# FPGA_MGT.net
KiCad netlist of a schematic drawn in Altium Designer
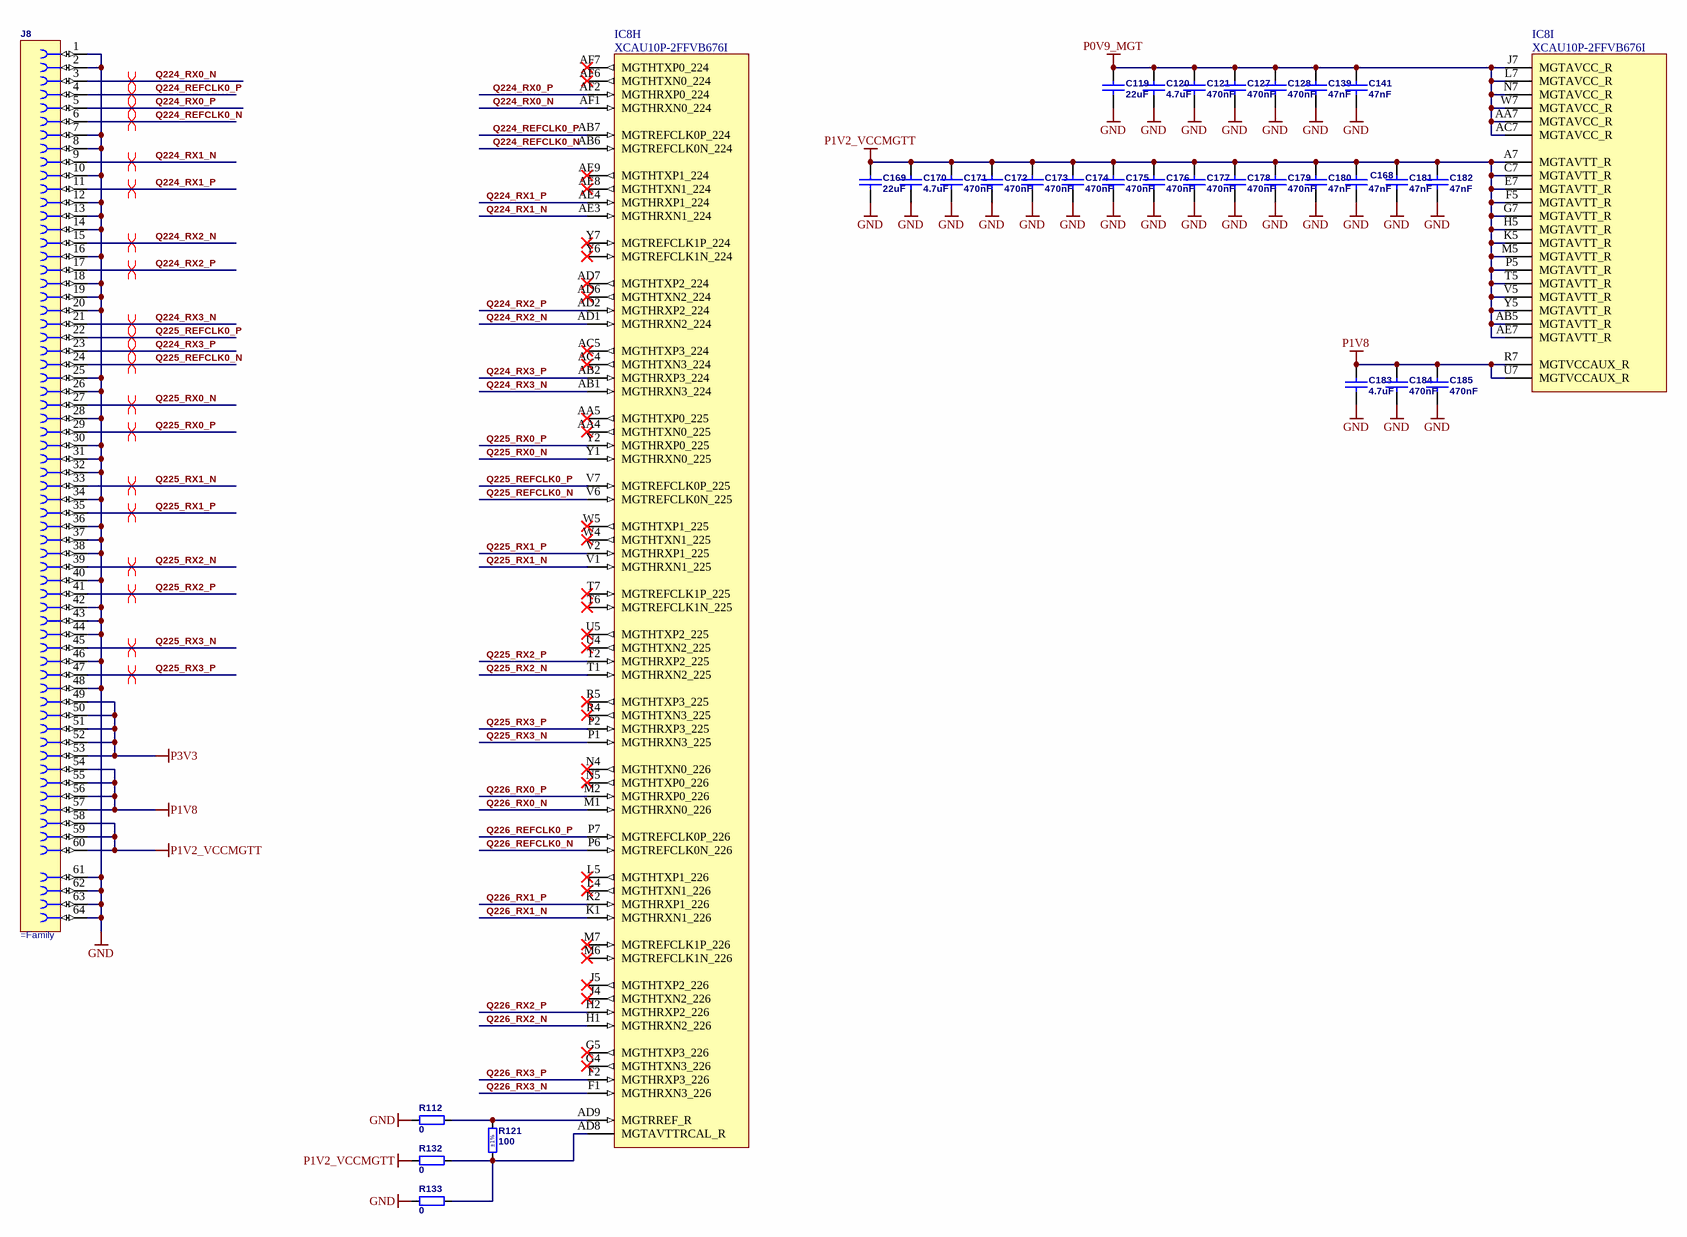
[diagram p0: FPGA_MGT.SchDoc]

(export (version "E")
  (design (tool "Eeschema 10.0.6"))
  (components
    (comp (ref "C119")
      (value "22uF")
      (footprint "CAPC1608X90N")
      (description "Non-polarised capacitor")
      (fields
        (field (name "PART NUMBER") "CC0603_22UF_6.3V_20%_X5R")
        (field (name "VOLTAGE") "6.3V")
        (field (name "AUTHOR") "CERN DEM JLC")
      )
      (libsource (lib "Capacitors") (part "Capacitor - non polarized"))
    )
    (comp (ref "C120")
      (value "4.7uF")
      (footprint "CAPC2012X135N")
      (description "Non-polarised capacitor")
      (fields
        (field (name "PART NUMBER") "CC0805_4.7UF_16V_10%_X7R")
        (field (name "VOLTAGE") "16V")
        (field (name "AUTHOR") "CERN DEM JLC")
      )
      (libsource (lib "Capacitors") (part "Capacitor - non polarized"))
    )
    (comp (ref "C121")
      (value "470nF")
      (footprint "CAPC1005X55N")
      (description "Non-polarised capacitor")
      (fields
        (field (name "PART NUMBER") "CC0402_470NF_16V_10%_X5R")
        (field (name "VOLTAGE") "16V")
        (field (name "AUTHOR") "CERN DEM JLC")
      )
      (libsource (lib "Capacitors") (part "Capacitor - non polarized"))
    )
    (comp (ref "C127")
      (value "470nF")
      (footprint "CAPC1005X55N")
      (description "Non-polarised capacitor")
      (fields
        (field (name "PART NUMBER") "CC0402_470NF_16V_10%_X5R")
        (field (name "VOLTAGE") "16V")
        (field (name "AUTHOR") "CERN DEM JLC")
      )
      (libsource (lib "Capacitors") (part "Capacitor - non polarized"))
    )
    (comp (ref "C128")
      (value "470nF")
      (footprint "CAPC1005X55N")
      (description "Non-polarised capacitor")
      (fields
        (field (name "PART NUMBER") "CC0402_470NF_16V_10%_X5R")
        (field (name "VOLTAGE") "16V")
        (field (name "AUTHOR") "CERN DEM JLC")
      )
      (libsource (lib "Capacitors") (part "Capacitor - non polarized"))
    )
    (comp (ref "C139")
      (value "47nF")
      (footprint "CAPC1005X55N")
      (description "Non-polarised capacitor")
      (fields
        (field (name "PART NUMBER") "CC0402_47NF_16V_10%_X7R")
        (field (name "VOLTAGE") "16V")
        (field (name "AUTHOR") "CERN DEM JLC")
      )
      (libsource (lib "Capacitors") (part "Capacitor - non polarized"))
    )
    (comp (ref "C141")
      (value "47nF")
      (footprint "CAPC1005X55N")
      (description "Non-polarised capacitor")
      (fields
        (field (name "PART NUMBER") "CC0402_47NF_16V_10%_X7R")
        (field (name "VOLTAGE") "16V")
        (field (name "AUTHOR") "CERN DEM JLC")
      )
      (libsource (lib "Capacitors") (part "Capacitor - non polarized"))
    )
    (comp (ref "C168")
      (value "47nF")
      (footprint "CAPC1005X55N")
      (description "Non-polarised capacitor")
      (fields
        (field (name "PART NUMBER") "CC0402_47NF_16V_10%_X7R")
        (field (name "VOLTAGE") "16V")
        (field (name "AUTHOR") "CERN DEM JLC")
      )
      (libsource (lib "Capacitors") (part "Capacitor - non polarized"))
    )
    (comp (ref "C169")
      (value "22uF")
      (footprint "CAPC1608X90N")
      (description "Non-polarised capacitor")
      (fields
        (field (name "PART NUMBER") "CC0603_22UF_6.3V_20%_X5R")
        (field (name "VOLTAGE") "6.3V")
        (field (name "AUTHOR") "CERN DEM JLC")
      )
      (libsource (lib "Capacitors") (part "Capacitor - non polarized"))
    )
    (comp (ref "C170")
      (value "4.7uF")
      (footprint "CAPC2012X135N")
      (description "Non-polarised capacitor")
      (fields
        (field (name "PART NUMBER") "CC0805_4.7UF_16V_10%_X7R")
        (field (name "VOLTAGE") "16V")
        (field (name "AUTHOR") "CERN DEM JLC")
      )
      (libsource (lib "Capacitors") (part "Capacitor - non polarized"))
    )
    (comp (ref "C171")
      (value "470nF")
      (footprint "CAPC1005X55N")
      (description "Non-polarised capacitor")
      (fields
        (field (name "PART NUMBER") "CC0402_470NF_16V_10%_X5R")
        (field (name "VOLTAGE") "16V")
        (field (name "AUTHOR") "CERN DEM JLC")
      )
      (libsource (lib "Capacitors") (part "Capacitor - non polarized"))
    )
    (comp (ref "C172")
      (value "470nF")
      (footprint "CAPC1005X55N")
      (description "Non-polarised capacitor")
      (fields
        (field (name "PART NUMBER") "CC0402_470NF_16V_10%_X5R")
        (field (name "VOLTAGE") "16V")
        (field (name "AUTHOR") "CERN DEM JLC")
      )
      (libsource (lib "Capacitors") (part "Capacitor - non polarized"))
    )
    (comp (ref "C173")
      (value "470nF")
      (footprint "CAPC1005X55N")
      (description "Non-polarised capacitor")
      (fields
        (field (name "PART NUMBER") "CC0402_470NF_16V_10%_X5R")
        (field (name "VOLTAGE") "16V")
        (field (name "AUTHOR") "CERN DEM JLC")
      )
      (libsource (lib "Capacitors") (part "Capacitor - non polarized"))
    )
    (comp (ref "C174")
      (value "470nF")
      (footprint "CAPC1005X55N")
      (description "Non-polarised capacitor")
      (fields
        (field (name "PART NUMBER") "CC0402_470NF_16V_10%_X5R")
        (field (name "VOLTAGE") "16V")
        (field (name "AUTHOR") "CERN DEM JLC")
      )
      (libsource (lib "Capacitors") (part "Capacitor - non polarized"))
    )
    (comp (ref "C175")
      (value "470nF")
      (footprint "CAPC1005X55N")
      (description "Non-polarised capacitor")
      (fields
        (field (name "PART NUMBER") "CC0402_470NF_16V_10%_X5R")
        (field (name "VOLTAGE") "16V")
        (field (name "AUTHOR") "CERN DEM JLC")
      )
      (libsource (lib "Capacitors") (part "Capacitor - non polarized"))
    )
    (comp (ref "C176")
      (value "470nF")
      (footprint "CAPC1005X55N")
      (description "Non-polarised capacitor")
      (fields
        (field (name "PART NUMBER") "CC0402_470NF_16V_10%_X5R")
        (field (name "VOLTAGE") "16V")
        (field (name "AUTHOR") "CERN DEM JLC")
      )
      (libsource (lib "Capacitors") (part "Capacitor - non polarized"))
    )
    (comp (ref "C177")
      (value "470nF")
      (footprint "CAPC1005X55N")
      (description "Non-polarised capacitor")
      (fields
        (field (name "PART NUMBER") "CC0402_470NF_16V_10%_X5R")
        (field (name "VOLTAGE") "16V")
        (field (name "AUTHOR") "CERN DEM JLC")
      )
      (libsource (lib "Capacitors") (part "Capacitor - non polarized"))
    )
    (comp (ref "C178")
      (value "470nF")
      (footprint "CAPC1005X55N")
      (description "Non-polarised capacitor")
      (fields
        (field (name "PART NUMBER") "CC0402_470NF_16V_10%_X5R")
        (field (name "VOLTAGE") "16V")
        (field (name "AUTHOR") "CERN DEM JLC")
      )
      (libsource (lib "Capacitors") (part "Capacitor - non polarized"))
    )
    (comp (ref "C179")
      (value "470nF")
      (footprint "CAPC1005X55N")
      (description "Non-polarised capacitor")
      (fields
        (field (name "PART NUMBER") "CC0402_470NF_16V_10%_X5R")
        (field (name "VOLTAGE") "16V")
        (field (name "AUTHOR") "CERN DEM JLC")
      )
      (libsource (lib "Capacitors") (part "Capacitor - non polarized"))
    )
    (comp (ref "C180")
      (value "47nF")
      (footprint "CAPC1005X55N")
      (description "Non-polarised capacitor")
      (fields
        (field (name "PART NUMBER") "CC0402_47NF_16V_10%_X7R")
        (field (name "VOLTAGE") "16V")
        (field (name "AUTHOR") "CERN DEM JLC")
      )
      (libsource (lib "Capacitors") (part "Capacitor - non polarized"))
    )
    (comp (ref "C181")
      (value "47nF")
      (footprint "CAPC1005X55N")
      (description "Non-polarised capacitor")
      (fields
        (field (name "PART NUMBER") "CC0402_47NF_16V_10%_X7R")
        (field (name "VOLTAGE") "16V")
        (field (name "AUTHOR") "CERN DEM JLC")
      )
      (libsource (lib "Capacitors") (part "Capacitor - non polarized"))
    )
    (comp (ref "C182")
      (value "47nF")
      (footprint "CAPC1005X55N")
      (description "Non-polarised capacitor")
      (fields
        (field (name "PART NUMBER") "CC0402_47NF_16V_10%_X7R")
        (field (name "VOLTAGE") "16V")
        (field (name "AUTHOR") "CERN DEM JLC")
      )
      (libsource (lib "Capacitors") (part "Capacitor - non polarized"))
    )
    (comp (ref "C183")
      (value "4.7uF")
      (footprint "CAPC2012X135N")
      (description "Non-polarised capacitor")
      (fields
        (field (name "PART NUMBER") "CC0805_4.7UF_16V_10%_X7R")
        (field (name "VOLTAGE") "16V")
        (field (name "AUTHOR") "CERN DEM JLC")
      )
      (libsource (lib "Capacitors") (part "Capacitor - non polarized"))
    )
    (comp (ref "C184")
      (value "470nF")
      (footprint "CAPC1005X55N")
      (description "Non-polarised capacitor")
      (fields
        (field (name "PART NUMBER") "CC0402_470NF_16V_10%_X5R")
        (field (name "VOLTAGE") "16V")
        (field (name "AUTHOR") "CERN DEM JLC")
      )
      (libsource (lib "Capacitors") (part "Capacitor - non polarized"))
    )
    (comp (ref "C185")
      (value "470nF")
      (footprint "CAPC1005X55N")
      (description "Non-polarised capacitor")
      (fields
        (field (name "PART NUMBER") "CC0402_470NF_16V_10%_X5R")
        (field (name "VOLTAGE") "16V")
        (field (name "AUTHOR") "CERN DEM JLC")
      )
      (libsource (lib "Capacitors") (part "Capacitor - non polarized"))
    )
    (comp (ref "IC8")
      (value "XCAU10P-2FFVB676I")
      (footprint "BGA676C100P26X26_2700X2700X350")
      (description "Artix UltraScale + Field Programmable Gate Array (FPGA), 676-Pin BGA, Industrial Grade")
      (fields (field (name "MANUFACTURER") "AMD") (field (name "AUTHOR") "CERN DEM HF"))
      (libsource (lib "ICs And Semiconductors") (part "XCAU10P-2FFVB676I"))
    )
    (comp (ref "J8")
      (value "~")
      (footprint "SAMTEC_QSH-030-01-L-D-A")
      (description "Connector 60 Female + 4 GND")
      (fields
        (field (name "PART NUMBER") "SAMTEC_QSH-030-01-L-D-A")
        (field (name "MANUFACTURER") "SAMTEC")
        (field (name "AUTHOR") "CERN DEM JLC")
      )
      (libsource (lib "Connectors") (part "Connector 60 Female + 4 GND"))
    )
    (comp (ref "R112")
      (value "0")
      (footprint "RESC1005X40N")
      (description "Resistor")
      (fields
        (field (name "PART NUMBER") "R0402_0R_JUMPER")
        (field (name "MANUFACTURER") "GENERIC")
        (field (name "AUTHOR") "CERN DEM JLC")
      )
      (libsource (lib "Resistors") (part "Resistor"))
    )
    (comp (ref "R121")
      (value "100")
      (footprint "RESC1005X40N")
      (description "Resistor - 1%")
      (fields
        (field (name "TOLERANCE") "±1%")
        (field (name "PART NUMBER") "R0402_100R_1%_0.0625W_100PPM")
        (field (name "POWER") "0.0625W")
        (field (name "AUTHOR") "CERN DEM JLC")
      )
      (libsource (lib "Resistors") (part "Resistor - 1%"))
    )
    (comp (ref "R132")
      (value "0")
      (footprint "RESC1005X40N")
      (description "Resistor")
      (fields
        (field (name "PART NUMBER") "R0402_0R_JUMPER")
        (field (name "MANUFACTURER") "GENERIC")
        (field (name "AUTHOR") "CERN DEM JLC")
      )
      (libsource (lib "Resistors") (part "Resistor"))
    )
    (comp (ref "R133")
      (value "0")
      (footprint "RESC1005X40N")
      (description "Resistor")
      (fields
        (field (name "PART NUMBER") "R0402_0R_JUMPER")
        (field (name "MANUFACTURER") "GENERIC")
        (field (name "AUTHOR") "CERN DEM JLC")
      )
      (libsource (lib "Resistors") (part "Resistor"))
    )
  )
  (nets
    (net (code "1") (name "/Q224_REFCLK0_N") (class "Default")
      (node (ref "IC8") (pin "AB6") (pinfunction "MGTREFCLK0N_224_AB6") (pintype "input"))
      (node (ref "J8") (pin "6") (pinfunction "6_6") (pintype "bidirectional"))
    )
    (net (code "2") (name "/Q224_REFCLK0_P") (class "Default")
      (node (ref "IC8") (pin "AB7") (pinfunction "MGTREFCLK0P_224_AB7") (pintype "input"))
      (node (ref "J8") (pin "4") (pinfunction "4_4") (pintype "bidirectional"))
    )
    (net (code "3") (name "/Q224_RX0_N") (class "Default")
      (node (ref "IC8") (pin "AF1") (pinfunction "MGTHRXN0_224_AF1") (pintype "input"))
      (node (ref "J8") (pin "3") (pinfunction "3_3") (pintype "bidirectional"))
    )
    (net (code "4") (name "/Q224_RX0_P") (class "Default")
      (node (ref "IC8") (pin "AF2") (pinfunction "MGTHRXP0_224_AF2") (pintype "input"))
      (node (ref "J8") (pin "5") (pinfunction "5_5") (pintype "bidirectional"))
    )
    (net (code "5") (name "/Q224_RX1_N") (class "Default")
      (node (ref "IC8") (pin "AE3") (pinfunction "MGTHRXN1_224_AE3") (pintype "input"))
      (node (ref "J8") (pin "9") (pinfunction "9_9") (pintype "bidirectional"))
    )
    (net (code "6") (name "/Q224_RX1_P") (class "Default")
      (node (ref "IC8") (pin "AE4") (pinfunction "MGTHRXP1_224_AE4") (pintype "input"))
      (node (ref "J8") (pin "11") (pinfunction "11_11") (pintype "bidirectional"))
    )
    (net (code "7") (name "/Q224_RX2_N") (class "Default")
      (node (ref "IC8") (pin "AD1") (pinfunction "MGTHRXN2_224_AD1") (pintype "input"))
      (node (ref "J8") (pin "15") (pinfunction "15_15") (pintype "bidirectional"))
    )
    (net (code "8") (name "/Q224_RX2_P") (class "Default")
      (node (ref "IC8") (pin "AD2") (pinfunction "MGTHRXP2_224_AD2") (pintype "input"))
      (node (ref "J8") (pin "17") (pinfunction "17_17") (pintype "bidirectional"))
    )
    (net (code "9") (name "/Q224_RX3_N") (class "Default")
      (node (ref "IC8") (pin "AB1") (pinfunction "MGTHRXN3_224_AB1") (pintype "input"))
      (node (ref "J8") (pin "21") (pinfunction "21_21") (pintype "bidirectional"))
    )
    (net (code "10") (name "/Q224_RX3_P") (class "Default")
      (node (ref "IC8") (pin "AB2") (pinfunction "MGTHRXP3_224_AB2") (pintype "input"))
      (node (ref "J8") (pin "23") (pinfunction "23_23") (pintype "bidirectional"))
    )
    (net (code "11") (name "/Q225_REFCLK0_N") (class "Default")
      (node (ref "IC8") (pin "V6") (pinfunction "MGTREFCLK0N_225_V6") (pintype "input"))
      (node (ref "J8") (pin "24") (pinfunction "24_24") (pintype "bidirectional"))
    )
    (net (code "12") (name "/Q225_REFCLK0_P") (class "Default")
      (node (ref "IC8") (pin "V7") (pinfunction "MGTREFCLK0P_225_V7") (pintype "input"))
      (node (ref "J8") (pin "22") (pinfunction "22_22") (pintype "bidirectional"))
    )
    (net (code "13") (name "/Q225_RX0_N") (class "Default")
      (node (ref "IC8") (pin "Y1") (pinfunction "MGTHRXN0_225_Y1") (pintype "input"))
      (node (ref "J8") (pin "27") (pinfunction "27_27") (pintype "bidirectional"))
    )
    (net (code "14") (name "/Q225_RX0_P") (class "Default")
      (node (ref "IC8") (pin "Y2") (pinfunction "MGTHRXP0_225_Y2") (pintype "input"))
      (node (ref "J8") (pin "29") (pinfunction "29_29") (pintype "bidirectional"))
    )
    (net (code "15") (name "/Q225_RX1_N") (class "Default")
      (node (ref "IC8") (pin "V1") (pinfunction "MGTHRXN1_225_V1") (pintype "input"))
      (node (ref "J8") (pin "33") (pinfunction "33_33") (pintype "bidirectional"))
    )
    (net (code "16") (name "/Q225_RX1_P") (class "Default")
      (node (ref "IC8") (pin "V2") (pinfunction "MGTHRXP1_225_V2") (pintype "input"))
      (node (ref "J8") (pin "35") (pinfunction "35_35") (pintype "bidirectional"))
    )
    (net (code "17") (name "/Q225_RX2_N") (class "Default")
      (node (ref "IC8") (pin "T1") (pinfunction "MGTHRXN2_225_T1") (pintype "input"))
      (node (ref "J8") (pin "39") (pinfunction "39_39") (pintype "bidirectional"))
    )
    (net (code "18") (name "/Q225_RX2_P") (class "Default")
      (node (ref "IC8") (pin "T2") (pinfunction "MGTHRXP2_225_T2") (pintype "input"))
      (node (ref "J8") (pin "41") (pinfunction "41_41") (pintype "bidirectional"))
    )
    (net (code "19") (name "/Q225_RX3_N") (class "Default")
      (node (ref "IC8") (pin "P1") (pinfunction "MGTHRXN3_225_P1") (pintype "input"))
      (node (ref "J8") (pin "45") (pinfunction "45_45") (pintype "bidirectional"))
    )
    (net (code "20") (name "/Q225_RX3_P") (class "Default")
      (node (ref "IC8") (pin "P2") (pinfunction "MGTHRXP3_225_P2") (pintype "input"))
      (node (ref "J8") (pin "47") (pinfunction "47_47") (pintype "bidirectional"))
    )
    (net (code "21") (name "/Q226_REFCLK0_N") (class "Default")
      (node (ref "IC8") (pin "P6") (pinfunction "MGTREFCLK0N_226_P6") (pintype "input"))
    )
    (net (code "22") (name "/Q226_REFCLK0_P") (class "Default")
      (node (ref "IC8") (pin "P7") (pinfunction "MGTREFCLK0P_226_P7") (pintype "input"))
    )
    (net (code "23") (name "/Q226_RX0_N") (class "Default")
      (node (ref "IC8") (pin "M1") (pinfunction "MGTHRXN0_226_M1") (pintype "input"))
    )
    (net (code "24") (name "/Q226_RX0_P") (class "Default")
      (node (ref "IC8") (pin "M2") (pinfunction "MGTHRXP0_226_M2") (pintype "input"))
    )
    (net (code "25") (name "/Q226_RX1_N") (class "Default")
      (node (ref "IC8") (pin "K1") (pinfunction "MGTHRXN1_226_K1") (pintype "input"))
    )
    (net (code "26") (name "/Q226_RX1_P") (class "Default")
      (node (ref "IC8") (pin "K2") (pinfunction "MGTHRXP1_226_K2") (pintype "input"))
    )
    (net (code "27") (name "/Q226_RX2_N") (class "Default")
      (node (ref "IC8") (pin "H1") (pinfunction "MGTHRXN2_226_H1") (pintype "input"))
    )
    (net (code "28") (name "/Q226_RX2_P") (class "Default")
      (node (ref "IC8") (pin "H2") (pinfunction "MGTHRXP2_226_H2") (pintype "input"))
    )
    (net (code "29") (name "/Q226_RX3_N") (class "Default")
      (node (ref "IC8") (pin "F1") (pinfunction "MGTHRXN3_226_F1") (pintype "input"))
    )
    (net (code "30") (name "/Q226_RX3_P") (class "Default")
      (node (ref "IC8") (pin "F2") (pinfunction "MGTHRXP3_226_F2") (pintype "input"))
    )
    (net (code "31") (name "GND") (class "Default")
      (node (ref "C119") (pin "1") (pinfunction "1_1") (pintype "passive"))
      (node (ref "C120") (pin "1") (pinfunction "1_1") (pintype "passive"))
      (node (ref "C121") (pin "1") (pinfunction "1_1") (pintype "passive"))
      (node (ref "C127") (pin "1") (pinfunction "1_1") (pintype "passive"))
      (node (ref "C128") (pin "1") (pinfunction "1_1") (pintype "passive"))
      (node (ref "C139") (pin "1") (pinfunction "1_1") (pintype "passive"))
      (node (ref "C141") (pin "1") (pinfunction "1_1") (pintype "passive"))
      (node (ref "C168") (pin "1") (pinfunction "1_1") (pintype "passive"))
      (node (ref "C169") (pin "1") (pinfunction "1_1") (pintype "passive"))
      (node (ref "C170") (pin "1") (pinfunction "1_1") (pintype "passive"))
      (node (ref "C171") (pin "1") (pinfunction "1_1") (pintype "passive"))
      (node (ref "C172") (pin "1") (pinfunction "1_1") (pintype "passive"))
      (node (ref "C173") (pin "1") (pinfunction "1_1") (pintype "passive"))
      (node (ref "C174") (pin "1") (pinfunction "1_1") (pintype "passive"))
      (node (ref "C175") (pin "1") (pinfunction "1_1") (pintype "passive"))
      (node (ref "C176") (pin "1") (pinfunction "1_1") (pintype "passive"))
      (node (ref "C177") (pin "1") (pinfunction "1_1") (pintype "passive"))
      (node (ref "C178") (pin "1") (pinfunction "1_1") (pintype "passive"))
      (node (ref "C179") (pin "1") (pinfunction "1_1") (pintype "passive"))
      (node (ref "C180") (pin "1") (pinfunction "1_1") (pintype "passive"))
      (node (ref "C181") (pin "1") (pinfunction "1_1") (pintype "passive"))
      (node (ref "C182") (pin "1") (pinfunction "1_1") (pintype "passive"))
      (node (ref "C183") (pin "1") (pinfunction "1_1") (pintype "passive"))
      (node (ref "C184") (pin "1") (pinfunction "1_1") (pintype "passive"))
      (node (ref "C185") (pin "1") (pinfunction "1_1") (pintype "passive"))
      (node (ref "J8") (pin "1") (pinfunction "1_1") (pintype "bidirectional"))
      (node (ref "J8") (pin "10") (pinfunction "10_10") (pintype "bidirectional"))
      (node (ref "J8") (pin "12") (pinfunction "12_12") (pintype "bidirectional"))
      (node (ref "J8") (pin "13") (pinfunction "13_13") (pintype "bidirectional"))
      (node (ref "J8") (pin "14") (pinfunction "14_14") (pintype "bidirectional"))
      (node (ref "J8") (pin "16") (pinfunction "16_16") (pintype "bidirectional"))
      (node (ref "J8") (pin "18") (pinfunction "18_18") (pintype "bidirectional"))
      (node (ref "J8") (pin "19") (pinfunction "19_19") (pintype "bidirectional"))
      (node (ref "J8") (pin "2") (pinfunction "2_2") (pintype "bidirectional"))
      (node (ref "J8") (pin "20") (pinfunction "20_20") (pintype "bidirectional"))
      (node (ref "J8") (pin "25") (pinfunction "25_25") (pintype "bidirectional"))
      (node (ref "J8") (pin "26") (pinfunction "26_26") (pintype "bidirectional"))
      (node (ref "J8") (pin "28") (pinfunction "28_28") (pintype "bidirectional"))
      (node (ref "J8") (pin "30") (pinfunction "30_30") (pintype "bidirectional"))
      (node (ref "J8") (pin "31") (pinfunction "31_31") (pintype "bidirectional"))
      (node (ref "J8") (pin "32") (pinfunction "32_32") (pintype "bidirectional"))
      (node (ref "J8") (pin "34") (pinfunction "34_34") (pintype "bidirectional"))
      (node (ref "J8") (pin "36") (pinfunction "36_36") (pintype "bidirectional"))
      (node (ref "J8") (pin "37") (pinfunction "37_37") (pintype "bidirectional"))
      (node (ref "J8") (pin "38") (pinfunction "38_38") (pintype "bidirectional"))
      (node (ref "J8") (pin "40") (pinfunction "40_40") (pintype "bidirectional"))
      (node (ref "J8") (pin "42") (pinfunction "42_42") (pintype "bidirectional"))
      (node (ref "J8") (pin "43") (pinfunction "43_43") (pintype "bidirectional"))
      (node (ref "J8") (pin "44") (pinfunction "44_44") (pintype "bidirectional"))
      (node (ref "J8") (pin "46") (pinfunction "46_46") (pintype "bidirectional"))
      (node (ref "J8") (pin "48") (pinfunction "48_48") (pintype "bidirectional"))
      (node (ref "J8") (pin "61") (pinfunction "61_61") (pintype "bidirectional"))
      (node (ref "J8") (pin "62") (pinfunction "62_62") (pintype "bidirectional"))
      (node (ref "J8") (pin "63") (pinfunction "63_63") (pintype "bidirectional"))
      (node (ref "J8") (pin "64") (pinfunction "64_64") (pintype "bidirectional"))
      (node (ref "J8") (pin "7") (pinfunction "7_7") (pintype "bidirectional"))
      (node (ref "J8") (pin "8") (pinfunction "8_8") (pintype "bidirectional"))
      (node (ref "R112") (pin "1") (pinfunction "1_1") (pintype "passive"))
      (node (ref "R133") (pin "1") (pinfunction "1_1") (pintype "passive"))
    )
    (net (code "32") (name "Net-(IC8H-MGTAVTTRCAL_R)") (class "Default")
      (node (ref "IC8") (pin "AD8") (pinfunction "MGTAVTTRCAL_R_AD8") (pintype "passive"))
      (node (ref "R121") (pin "2") (pinfunction "2_2") (pintype "passive"))
      (node (ref "R132") (pin "2") (pinfunction "2_2") (pintype "passive"))
      (node (ref "R133") (pin "2") (pinfunction "2_2") (pintype "passive"))
    )
    (net (code "33") (name "Net-(IC8H-MGTRREF_R)") (class "Default")
      (node (ref "IC8") (pin "AD9") (pinfunction "MGTRREF_R_AD9") (pintype "input"))
      (node (ref "R112") (pin "2") (pinfunction "2_2") (pintype "passive"))
      (node (ref "R121") (pin "1") (pinfunction "1_1") (pintype "passive"))
    )
    (net (code "34") (name "P0V9_MGT") (class "Default")
      (node (ref "C119") (pin "2") (pinfunction "2_2") (pintype "passive"))
      (node (ref "C120") (pin "2") (pinfunction "2_2") (pintype "passive"))
      (node (ref "C121") (pin "2") (pinfunction "2_2") (pintype "passive"))
      (node (ref "C127") (pin "2") (pinfunction "2_2") (pintype "passive"))
      (node (ref "C128") (pin "2") (pinfunction "2_2") (pintype "passive"))
      (node (ref "C139") (pin "2") (pinfunction "2_2") (pintype "passive"))
      (node (ref "C141") (pin "2") (pinfunction "2_2") (pintype "passive"))
      (node (ref "IC8") (pin "AA7") (pinfunction "MGTAVCC_R_AA7") (pintype "power_in"))
      (node (ref "IC8") (pin "AC7") (pinfunction "MGTAVCC_R_AC7") (pintype "power_in"))
      (node (ref "IC8") (pin "J7") (pinfunction "MGTAVCC_R_J7") (pintype "power_in"))
      (node (ref "IC8") (pin "L7") (pinfunction "MGTAVCC_R_L7") (pintype "power_in"))
      (node (ref "IC8") (pin "N7") (pinfunction "MGTAVCC_R_N7") (pintype "power_in"))
      (node (ref "IC8") (pin "W7") (pinfunction "MGTAVCC_R_W7") (pintype "power_in"))
    )
    (net (code "35") (name "P1V2_VCCMGTT") (class "Default")
      (node (ref "C168") (pin "2") (pinfunction "2_2") (pintype "passive"))
      (node (ref "C169") (pin "2") (pinfunction "2_2") (pintype "passive"))
      (node (ref "C170") (pin "2") (pinfunction "2_2") (pintype "passive"))
      (node (ref "C171") (pin "2") (pinfunction "2_2") (pintype "passive"))
      (node (ref "C172") (pin "2") (pinfunction "2_2") (pintype "passive"))
      (node (ref "C173") (pin "2") (pinfunction "2_2") (pintype "passive"))
      (node (ref "C174") (pin "2") (pinfunction "2_2") (pintype "passive"))
      (node (ref "C175") (pin "2") (pinfunction "2_2") (pintype "passive"))
      (node (ref "C176") (pin "2") (pinfunction "2_2") (pintype "passive"))
      (node (ref "C177") (pin "2") (pinfunction "2_2") (pintype "passive"))
      (node (ref "C178") (pin "2") (pinfunction "2_2") (pintype "passive"))
      (node (ref "C179") (pin "2") (pinfunction "2_2") (pintype "passive"))
      (node (ref "C180") (pin "2") (pinfunction "2_2") (pintype "passive"))
      (node (ref "C181") (pin "2") (pinfunction "2_2") (pintype "passive"))
      (node (ref "C182") (pin "2") (pinfunction "2_2") (pintype "passive"))
      (node (ref "IC8") (pin "A7") (pinfunction "MGTAVTT_R_A7") (pintype "power_in"))
      (node (ref "IC8") (pin "AB5") (pinfunction "MGTAVTT_R_AB5") (pintype "power_in"))
      (node (ref "IC8") (pin "AE7") (pinfunction "MGTAVTT_R_AE7") (pintype "power_in"))
      (node (ref "IC8") (pin "C7") (pinfunction "MGTAVTT_R_C7") (pintype "power_in"))
      (node (ref "IC8") (pin "E7") (pinfunction "MGTAVTT_R_E7") (pintype "power_in"))
      (node (ref "IC8") (pin "F5") (pinfunction "MGTAVTT_R_F5") (pintype "power_in"))
      (node (ref "IC8") (pin "G7") (pinfunction "MGTAVTT_R_G7") (pintype "power_in"))
      (node (ref "IC8") (pin "H5") (pinfunction "MGTAVTT_R_H5") (pintype "power_in"))
      (node (ref "IC8") (pin "K5") (pinfunction "MGTAVTT_R_K5") (pintype "power_in"))
      (node (ref "IC8") (pin "M5") (pinfunction "MGTAVTT_R_M5") (pintype "power_in"))
      (node (ref "IC8") (pin "P5") (pinfunction "MGTAVTT_R_P5") (pintype "power_in"))
      (node (ref "IC8") (pin "T5") (pinfunction "MGTAVTT_R_T5") (pintype "power_in"))
      (node (ref "IC8") (pin "V5") (pinfunction "MGTAVTT_R_V5") (pintype "power_in"))
      (node (ref "IC8") (pin "Y5") (pinfunction "MGTAVTT_R_Y5") (pintype "power_in"))
      (node (ref "J8") (pin "58") (pinfunction "58_58") (pintype "bidirectional"))
      (node (ref "J8") (pin "59") (pinfunction "59_59") (pintype "bidirectional"))
      (node (ref "J8") (pin "60") (pinfunction "60_60") (pintype "bidirectional"))
      (node (ref "R132") (pin "1") (pinfunction "1_1") (pintype "passive"))
    )
    (net (code "36") (name "P1V8") (class "Default")
      (node (ref "C183") (pin "2") (pinfunction "2_2") (pintype "passive"))
      (node (ref "C184") (pin "2") (pinfunction "2_2") (pintype "passive"))
      (node (ref "C185") (pin "2") (pinfunction "2_2") (pintype "passive"))
      (node (ref "IC8") (pin "R7") (pinfunction "MGTVCCAUX_R_R7") (pintype "power_in"))
      (node (ref "IC8") (pin "U7") (pinfunction "MGTVCCAUX_R_U7") (pintype "power_in"))
      (node (ref "J8") (pin "54") (pinfunction "54_54") (pintype "bidirectional"))
      (node (ref "J8") (pin "55") (pinfunction "55_55") (pintype "bidirectional"))
      (node (ref "J8") (pin "56") (pinfunction "56_56") (pintype "bidirectional"))
      (node (ref "J8") (pin "57") (pinfunction "57_57") (pintype "bidirectional"))
    )
    (net (code "37") (name "P3V3") (class "Default")
      (node (ref "J8") (pin "49") (pinfunction "49_49") (pintype "bidirectional"))
      (node (ref "J8") (pin "50") (pinfunction "50_50") (pintype "bidirectional"))
      (node (ref "J8") (pin "51") (pinfunction "51_51") (pintype "bidirectional"))
      (node (ref "J8") (pin "52") (pinfunction "52_52") (pintype "bidirectional"))
      (node (ref "J8") (pin "53") (pinfunction "53_53") (pintype "bidirectional"))
    )
    (net (code "38") (name "unconnected-(IC8H-MGTHTXN0_224-PadAF6)") (class "Default")
      (node (ref "IC8") (pin "AF6") (pinfunction "MGTHTXN0_224_AF6") (pintype "output+no_connect"))
    )
    (net (code "39") (name "unconnected-(IC8H-MGTHTXN0_225-PadAA4)") (class "Default")
      (node (ref "IC8") (pin "AA4") (pinfunction "MGTHTXN0_225_AA4") (pintype "output+no_connect"))
    )
    (net (code "40") (name "unconnected-(IC8H-MGTHTXN0_226-PadN4)") (class "Default")
      (node (ref "IC8") (pin "N4") (pinfunction "MGTHTXN0_226_N4") (pintype "output+no_connect"))
    )
    (net (code "41") (name "unconnected-(IC8H-MGTHTXN1_224-PadAE8)") (class "Default")
      (node (ref "IC8") (pin "AE8") (pinfunction "MGTHTXN1_224_AE8") (pintype "output+no_connect"))
    )
    (net (code "42") (name "unconnected-(IC8H-MGTHTXN1_225-PadW4)") (class "Default")
      (node (ref "IC8") (pin "W4") (pinfunction "MGTHTXN1_225_W4") (pintype "output+no_connect"))
    )
    (net (code "43") (name "unconnected-(IC8H-MGTHTXN1_226-PadL4)") (class "Default")
      (node (ref "IC8") (pin "L4") (pinfunction "MGTHTXN1_226_L4") (pintype "output+no_connect"))
    )
    (net (code "44") (name "unconnected-(IC8H-MGTHTXN2_224-PadAD6)") (class "Default")
      (node (ref "IC8") (pin "AD6") (pinfunction "MGTHTXN2_224_AD6") (pintype "output+no_connect"))
    )
    (net (code "45") (name "unconnected-(IC8H-MGTHTXN2_225-PadU4)") (class "Default")
      (node (ref "IC8") (pin "U4") (pinfunction "MGTHTXN2_225_U4") (pintype "output+no_connect"))
    )
    (net (code "46") (name "unconnected-(IC8H-MGTHTXN2_226-PadJ4)") (class "Default")
      (node (ref "IC8") (pin "J4") (pinfunction "MGTHTXN2_226_J4") (pintype "output+no_connect"))
    )
    (net (code "47") (name "unconnected-(IC8H-MGTHTXN3_224-PadAC4)") (class "Default")
      (node (ref "IC8") (pin "AC4") (pinfunction "MGTHTXN3_224_AC4") (pintype "output+no_connect"))
    )
    (net (code "48") (name "unconnected-(IC8H-MGTHTXN3_225-PadR4)") (class "Default")
      (node (ref "IC8") (pin "R4") (pinfunction "MGTHTXN3_225_R4") (pintype "output+no_connect"))
    )
    (net (code "49") (name "unconnected-(IC8H-MGTHTXN3_226-PadG4)") (class "Default")
      (node (ref "IC8") (pin "G4") (pinfunction "MGTHTXN3_226_G4") (pintype "output+no_connect"))
    )
    (net (code "50") (name "unconnected-(IC8H-MGTHTXP0_224-PadAF7)") (class "Default")
      (node (ref "IC8") (pin "AF7") (pinfunction "MGTHTXP0_224_AF7") (pintype "output+no_connect"))
    )
    (net (code "51") (name "unconnected-(IC8H-MGTHTXP0_225-PadAA5)") (class "Default")
      (node (ref "IC8") (pin "AA5") (pinfunction "MGTHTXP0_225_AA5") (pintype "output+no_connect"))
    )
    (net (code "52") (name "unconnected-(IC8H-MGTHTXP0_226-PadN5)") (class "Default")
      (node (ref "IC8") (pin "N5") (pinfunction "MGTHTXP0_226_N5") (pintype "output+no_connect"))
    )
    (net (code "53") (name "unconnected-(IC8H-MGTHTXP1_224-PadAE9)") (class "Default")
      (node (ref "IC8") (pin "AE9") (pinfunction "MGTHTXP1_224_AE9") (pintype "output+no_connect"))
    )
    (net (code "54") (name "unconnected-(IC8H-MGTHTXP1_225-PadW5)") (class "Default")
      (node (ref "IC8") (pin "W5") (pinfunction "MGTHTXP1_225_W5") (pintype "output+no_connect"))
    )
    (net (code "55") (name "unconnected-(IC8H-MGTHTXP1_226-PadL5)") (class "Default")
      (node (ref "IC8") (pin "L5") (pinfunction "MGTHTXP1_226_L5") (pintype "output+no_connect"))
    )
    (net (code "56") (name "unconnected-(IC8H-MGTHTXP2_224-PadAD7)") (class "Default")
      (node (ref "IC8") (pin "AD7") (pinfunction "MGTHTXP2_224_AD7") (pintype "output+no_connect"))
    )
    (net (code "57") (name "unconnected-(IC8H-MGTHTXP2_225-PadU5)") (class "Default")
      (node (ref "IC8") (pin "U5") (pinfunction "MGTHTXP2_225_U5") (pintype "output+no_connect"))
    )
    (net (code "58") (name "unconnected-(IC8H-MGTHTXP2_226-PadJ5)") (class "Default")
      (node (ref "IC8") (pin "J5") (pinfunction "MGTHTXP2_226_J5") (pintype "output+no_connect"))
    )
    (net (code "59") (name "unconnected-(IC8H-MGTHTXP3_224-PadAC5)") (class "Default")
      (node (ref "IC8") (pin "AC5") (pinfunction "MGTHTXP3_224_AC5") (pintype "output+no_connect"))
    )
    (net (code "60") (name "unconnected-(IC8H-MGTHTXP3_225-PadR5)") (class "Default")
      (node (ref "IC8") (pin "R5") (pinfunction "MGTHTXP3_225_R5") (pintype "output+no_connect"))
    )
    (net (code "61") (name "unconnected-(IC8H-MGTHTXP3_226-PadG5)") (class "Default")
      (node (ref "IC8") (pin "G5") (pinfunction "MGTHTXP3_226_G5") (pintype "output+no_connect"))
    )
    (net (code "62") (name "unconnected-(IC8H-MGTREFCLK1N_224-PadY6)") (class "Default")
      (node (ref "IC8") (pin "Y6") (pinfunction "MGTREFCLK1N_224_Y6") (pintype "input+no_connect"))
    )
    (net (code "63") (name "unconnected-(IC8H-MGTREFCLK1N_225-PadT6)") (class "Default")
      (node (ref "IC8") (pin "T6") (pinfunction "MGTREFCLK1N_225_T6") (pintype "input+no_connect"))
    )
    (net (code "64") (name "unconnected-(IC8H-MGTREFCLK1N_226-PadM6)") (class "Default")
      (node (ref "IC8") (pin "M6") (pinfunction "MGTREFCLK1N_226_M6") (pintype "input+no_connect"))
    )
    (net (code "65") (name "unconnected-(IC8H-MGTREFCLK1P_224-PadY7)") (class "Default")
      (node (ref "IC8") (pin "Y7") (pinfunction "MGTREFCLK1P_224_Y7") (pintype "input+no_connect"))
    )
    (net (code "66") (name "unconnected-(IC8H-MGTREFCLK1P_225-PadT7)") (class "Default")
      (node (ref "IC8") (pin "T7") (pinfunction "MGTREFCLK1P_225_T7") (pintype "input+no_connect"))
    )
    (net (code "67") (name "unconnected-(IC8H-MGTREFCLK1P_226-PadM7)") (class "Default")
      (node (ref "IC8") (pin "M7") (pinfunction "MGTREFCLK1P_226_M7") (pintype "input+no_connect"))
    )
  )
)
